# w14_MAKEYMAKEY-v03_2_3.net
KiCad netlist of a schematic drawn in EAGLE
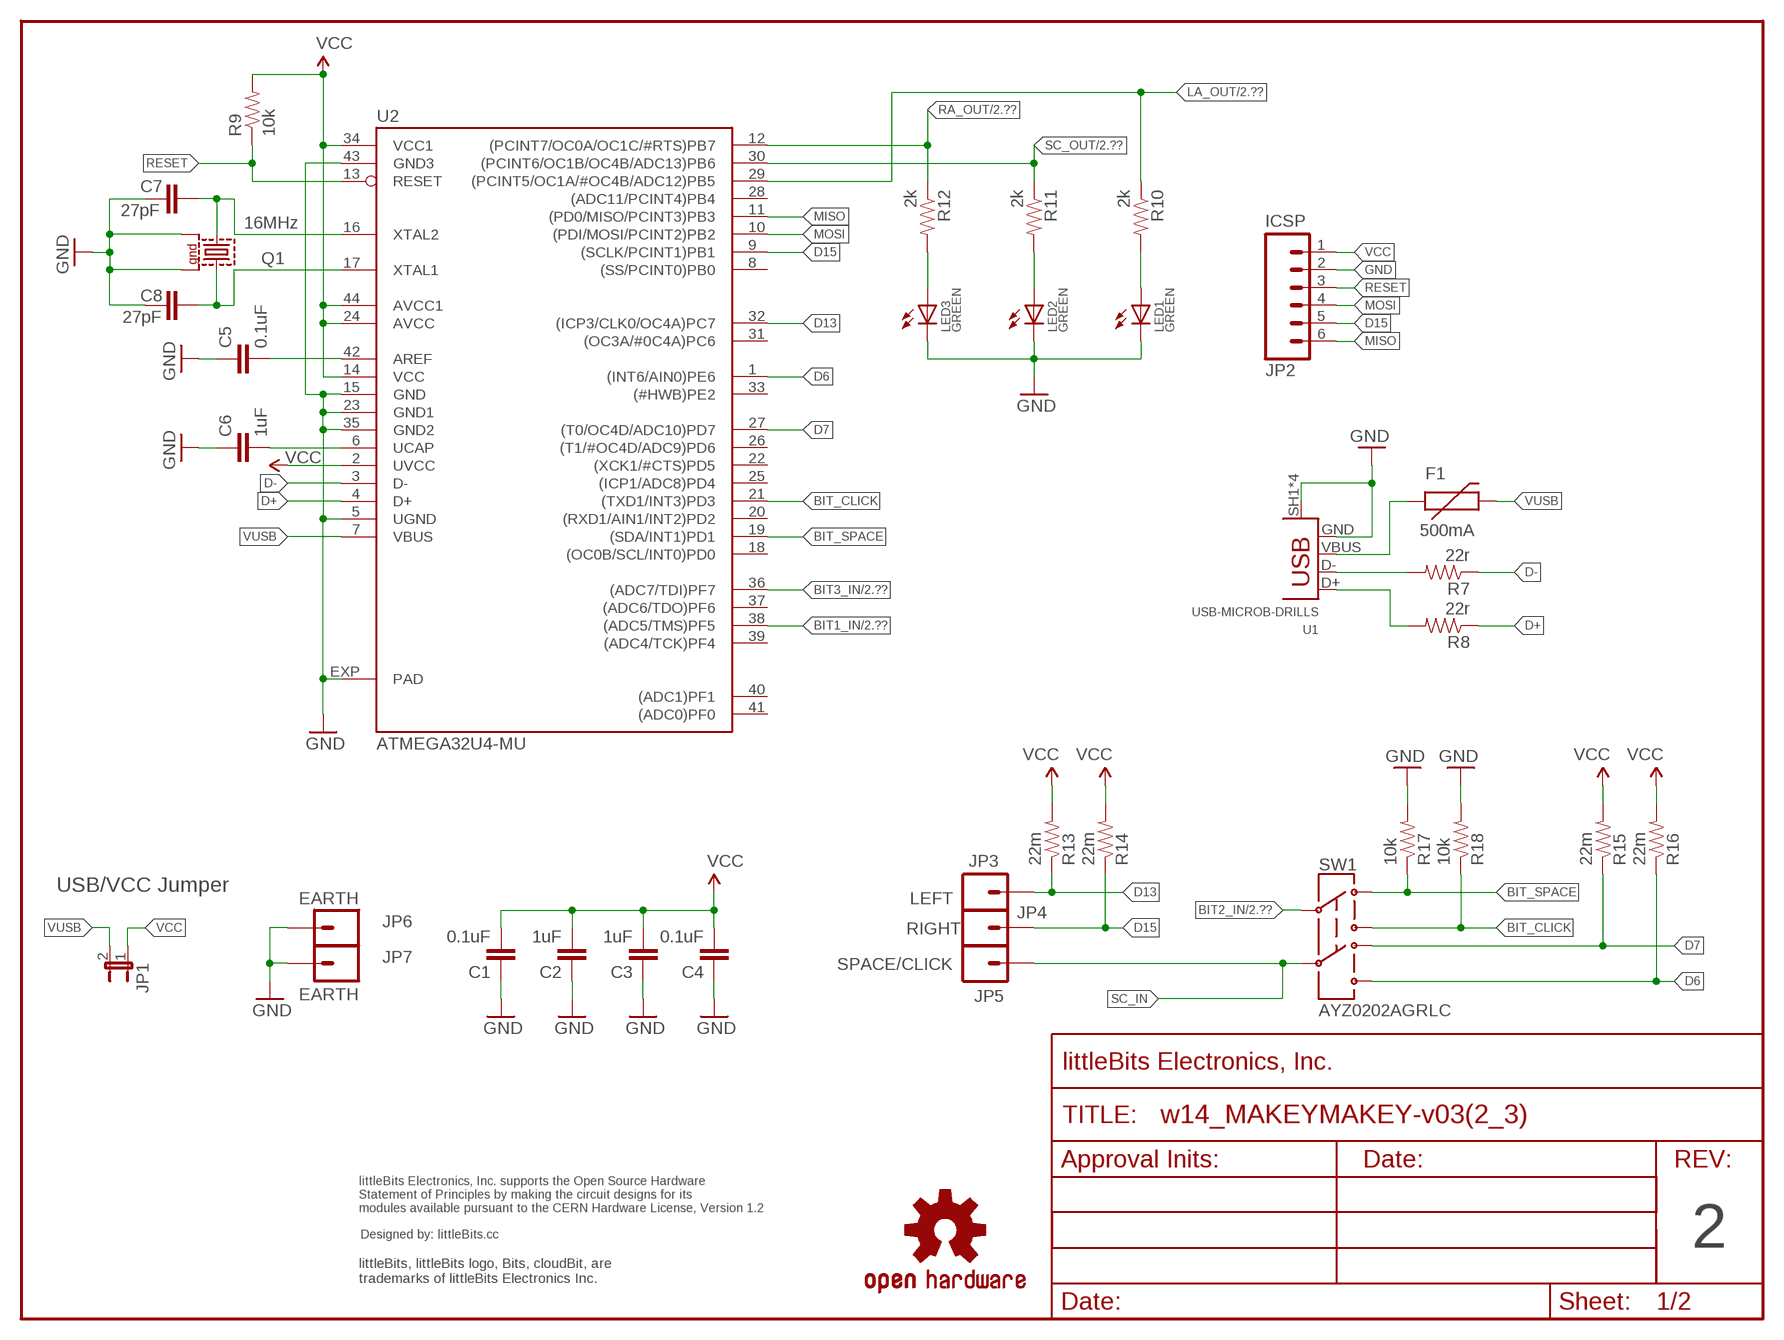
[diagram p0: schematic, sheet 1]
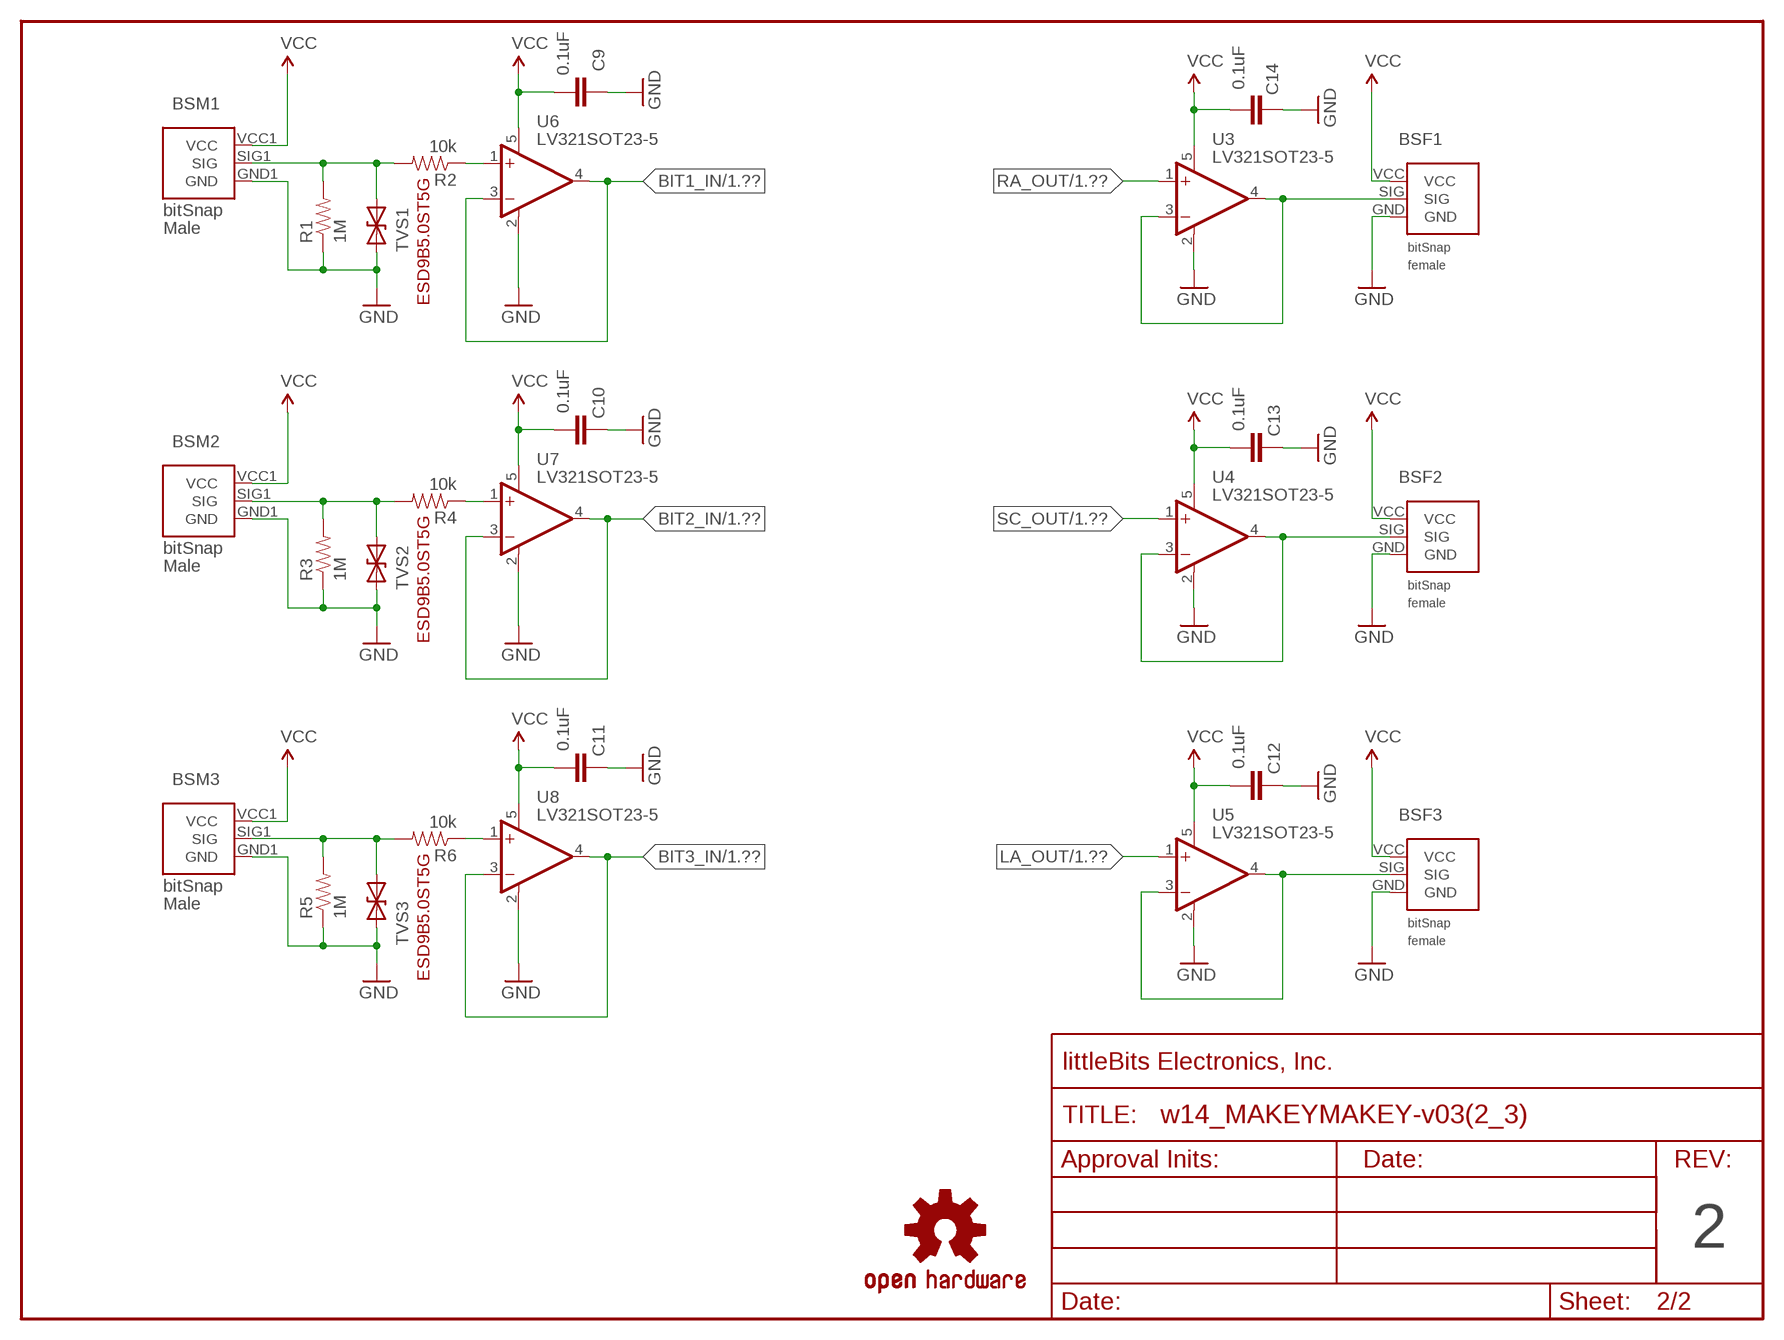
[diagram p1: schematic, sheet 2]

(export (version "E")
  (design (tool "Eeschema 10.0.6"))
  (components
    (comp (ref "C1")
      (value "0.1uF")
      (footprint "eagle-import:CAP-0603")
      (libsource (lib "eagle-import") (part "CAPCAP-0603"))
    )
    (comp (ref "C2")
      (value "1uF")
      (footprint "eagle-import:CAP-0603")
      (libsource (lib "eagle-import") (part "CAPCAP-0603"))
    )
    (comp (ref "C3")
      (value "1uF")
      (footprint "eagle-import:CAP-0603")
      (libsource (lib "eagle-import") (part "CAPCAP-0603"))
    )
    (comp (ref "C4")
      (value "0.1uF")
      (footprint "eagle-import:CAP-0603")
      (libsource (lib "eagle-import") (part "CAPCAP-0603"))
    )
    (comp (ref "C5")
      (value "0.1uF")
      (footprint "eagle-import:CAP-0603")
      (libsource (lib "eagle-import") (part "CAPCAP-0603"))
    )
    (comp (ref "C6")
      (value "1uF")
      (footprint "eagle-import:CAP-0603")
      (libsource (lib "eagle-import") (part "CAPCAP-0603"))
    )
    (comp (ref "C7")
      (value "27pF")
      (footprint "eagle-import:CAP-0603")
      (libsource (lib "eagle-import") (part "CAPCAP-0603"))
    )
    (comp (ref "C8")
      (value "27pF")
      (footprint "eagle-import:CAP-0603")
      (libsource (lib "eagle-import") (part "CAPCAP-0603"))
    )
    (comp (ref "F1")
      (value "500mA")
      (footprint "eagle-import:PTC-1206")
      (libsource (lib "eagle-import") (part "PTC"))
    )
    (comp (ref "JP1")
      (value "JUMPER-2SMD-NO")
      (footprint "eagle-import:SJ_2S-NO")
      (libsource (lib "eagle-import") (part "JUMPER-2SMD-NO"))
    )
    (comp (ref "JP2")
      (value "ICSP")
      (footprint "eagle-import:SIP6-SM-0.1IN-NOS.S.")
      (libsource (lib "eagle-import") (part "HRD-60.1INCH_NO_SILKSCREEN"))
    )
    (comp (ref "JP3")
      (value "LEFT")
      (footprint "eagle-import:1X01_ALLIGATOR_3MM")
      (libsource (lib "eagle-import") (part "M01ALLIGATOR-3MM"))
    )
    (comp (ref "JP4")
      (value "RIGHT")
      (footprint "eagle-import:1X01_ALLIGATOR_3MM")
      (libsource (lib "eagle-import") (part "M01ALLIGATOR-3MM"))
    )
    (comp (ref "JP5")
      (value "SPACE/CLICK")
      (footprint "eagle-import:1X01_ALLIGATOR_3MM")
      (libsource (lib "eagle-import") (part "M01ALLIGATOR-3MM"))
    )
    (comp (ref "JP6")
      (value "EARTH")
      (footprint "eagle-import:1X01_ALLIGATOR_3MM")
      (libsource (lib "eagle-import") (part "M01ALLIGATOR-3MM"))
    )
    (comp (ref "JP7")
      (value "EARTH")
      (footprint "eagle-import:1X01_ALLIGATOR_3MM")
      (libsource (lib "eagle-import") (part "M01ALLIGATOR-3MM"))
    )
    (comp (ref "LED1")
      (value "GREEN")
      (footprint "eagle-import:LED-1206")
      (libsource (lib "eagle-import") (part "LED1206"))
    )
    (comp (ref "LED2")
      (value "GREEN")
      (footprint "eagle-import:LED-1206")
      (libsource (lib "eagle-import") (part "LED1206"))
    )
    (comp (ref "LED3")
      (value "GREEN")
      (footprint "eagle-import:LED-1206")
      (libsource (lib "eagle-import") (part "LED1206"))
    )
    (comp (ref "Q1")
      (value "16MHz")
      (footprint "eagle-import:CRYSTAL-SMD-7B-SERIES-5X3.2MM")
      (fields (field (name "MFG") "TXC") (field (name "MPN") "7B SERIES"))
      (libsource (lib "eagle-import") (part "CRYSTAL-SMD-7B-SERIES-TXC"))
    )
    (comp (ref "R7")
      (value "22r")
      (footprint "eagle-import:RES-0603")
      (libsource (lib "eagle-import") (part "RESISTOR0603"))
    )
    (comp (ref "R8")
      (value "22r")
      (footprint "eagle-import:RES-0603")
      (libsource (lib "eagle-import") (part "RESISTOR0603"))
    )
    (comp (ref "R9")
      (value "10k")
      (footprint "eagle-import:RES-0603")
      (libsource (lib "eagle-import") (part "RESISTOR0603"))
    )
    (comp (ref "R10")
      (value "2k")
      (footprint "eagle-import:RES-0603")
      (libsource (lib "eagle-import") (part "RESISTOR0603"))
    )
    (comp (ref "R11")
      (value "2k")
      (footprint "eagle-import:RES-0603")
      (libsource (lib "eagle-import") (part "RESISTOR0603"))
    )
    (comp (ref "R12")
      (value "2k")
      (footprint "eagle-import:RES-0603")
      (libsource (lib "eagle-import") (part "RESISTOR0603"))
    )
    (comp (ref "R13")
      (value "22m")
      (footprint "eagle-import:RES-0603")
      (libsource (lib "eagle-import") (part "RESISTOR0603"))
    )
    (comp (ref "R14")
      (value "22m")
      (footprint "eagle-import:RES-0603")
      (libsource (lib "eagle-import") (part "RESISTOR0603"))
    )
    (comp (ref "R15")
      (value "22m")
      (footprint "eagle-import:RES-0603")
      (libsource (lib "eagle-import") (part "RESISTOR0603"))
    )
    (comp (ref "R16")
      (value "22m")
      (footprint "eagle-import:RES-0603")
      (libsource (lib "eagle-import") (part "RESISTOR0603"))
    )
    (comp (ref "R17")
      (value "10k")
      (footprint "eagle-import:RES-0603")
      (libsource (lib "eagle-import") (part "RESISTOR0603"))
    )
    (comp (ref "R18")
      (value "10k")
      (footprint "eagle-import:RES-0603")
      (libsource (lib "eagle-import") (part "RESISTOR0603"))
    )
    (comp (ref "SW1")
      (value "AYZ0202AGRLC")
      (footprint "eagle-import:AYZ0202")
      (libsource (lib "eagle-import") (part "AYZ0202"))
    )
    (comp (ref "U$1")
      (value "OSHWCREDIT")
      (footprint "eagle-import:OSHWCREDIT")
      (libsource (lib "eagle-import") (part "OSHWCREDIT"))
    )
    (comp (ref "U$58")
      (value "FRAME-LETTER-OHWOHW")
      (footprint "eagle-import:FABDWG01-OHW")
      (libsource (lib "eagle-import") (part "FRAME-LETTER-OHWOHW"))
    )
    (comp (ref "U$70")
      (value "OSHW-LOGOL")
      (footprint "eagle-import:OSHW-LOGO-L")
      (libsource (lib "eagle-import") (part "OSHW-LOGOL"))
    )
    (comp (ref "U1")
      (value "USB-MICROB-DRILLS")
      (footprint "eagle-import:USB-MICROB-AUK-DRILLS")
      (fields (field (name "MFG") "AUK") (field (name "MPN") "MCSB5ABSW-4-GXX-R1K-H"))
      (libsource (lib "eagle-import") (part "USB-MICROB-DRILLS"))
    )
    (comp (ref "U2")
      (value "ATMEGA32U4-MU")
      (footprint "eagle-import:QFN44ML7X7")
      (libsource (lib "eagle-import") (part "ATMEGA32U4-XUMU"))
    )
    (comp (ref "BSF1")
      (value "BITSNAP_V03_FEMALE")
      (footprint "eagle-import:BITSNAP_V03_FEMALE")
      (libsource (lib "eagle-import") (part "BITSNAP_V03_FEMALE"))
    )
    (comp (ref "BSF2")
      (value "BITSNAP_V03_FEMALE")
      (footprint "eagle-import:BITSNAP_V03_FEMALE")
      (libsource (lib "eagle-import") (part "BITSNAP_V03_FEMALE"))
    )
    (comp (ref "BSF3")
      (value "BITSNAP_V03_FEMALE")
      (footprint "eagle-import:BITSNAP_V03_FEMALE")
      (libsource (lib "eagle-import") (part "BITSNAP_V03_FEMALE"))
    )
    (comp (ref "BSM1")
      (value "BITSNAP_V03_MALE")
      (footprint "eagle-import:BITSNAP_V03_MALE")
      (libsource (lib "eagle-import") (part "BITSNAP_V03_MALE"))
    )
    (comp (ref "BSM2")
      (value "BITSNAP_V03_MALE")
      (footprint "eagle-import:BITSNAP_V03_MALE")
      (libsource (lib "eagle-import") (part "BITSNAP_V03_MALE"))
    )
    (comp (ref "BSM3")
      (value "BITSNAP_V03_MALE")
      (footprint "eagle-import:BITSNAP_V03_MALE")
      (libsource (lib "eagle-import") (part "BITSNAP_V03_MALE"))
    )
    (comp (ref "C9")
      (value "0.1uF")
      (footprint "eagle-import:CAP-0603")
      (libsource (lib "eagle-import") (part "CAPCAP-0603"))
    )
    (comp (ref "C10")
      (value "0.1uF")
      (footprint "eagle-import:CAP-0603")
      (libsource (lib "eagle-import") (part "CAPCAP-0603"))
    )
    (comp (ref "C11")
      (value "0.1uF")
      (footprint "eagle-import:CAP-0603")
      (libsource (lib "eagle-import") (part "CAPCAP-0603"))
    )
    (comp (ref "C12")
      (value "0.1uF")
      (footprint "eagle-import:CAP-0603")
      (libsource (lib "eagle-import") (part "CAPCAP-0603"))
    )
    (comp (ref "C13")
      (value "0.1uF")
      (footprint "eagle-import:CAP-0603")
      (libsource (lib "eagle-import") (part "CAPCAP-0603"))
    )
    (comp (ref "C14")
      (value "0.1uF")
      (footprint "eagle-import:CAP-0603")
      (libsource (lib "eagle-import") (part "CAPCAP-0603"))
    )
    (comp (ref "R1")
      (value "1M")
      (footprint "eagle-import:RES-0603")
      (libsource (lib "eagle-import") (part "RESISTOR0603"))
    )
    (comp (ref "R2")
      (value "10k")
      (footprint "eagle-import:RES-0603")
      (libsource (lib "eagle-import") (part "RESISTOR0603"))
    )
    (comp (ref "R3")
      (value "1M")
      (footprint "eagle-import:RES-0603")
      (libsource (lib "eagle-import") (part "RESISTOR0603"))
    )
    (comp (ref "R4")
      (value "10k")
      (footprint "eagle-import:RES-0603")
      (libsource (lib "eagle-import") (part "RESISTOR0603"))
    )
    (comp (ref "R5")
      (value "1M")
      (footprint "eagle-import:RES-0603")
      (libsource (lib "eagle-import") (part "RESISTOR0603"))
    )
    (comp (ref "R6")
      (value "10k")
      (footprint "eagle-import:RES-0603")
      (libsource (lib "eagle-import") (part "RESISTOR0603"))
    )
    (comp (ref "TVS1")
      (value "ESD9B5.0ST5G")
      (footprint "eagle-import:SOD-923")
      (fields (field (name "MPN") "ESD9B5.0ST5G"))
      (libsource (lib "eagle-import") (part "DIODE-TVSSOD-923"))
    )
    (comp (ref "TVS2")
      (value "ESD9B5.0ST5G")
      (footprint "eagle-import:SOD-923")
      (fields (field (name "MPN") "ESD9B5.0ST5G"))
      (libsource (lib "eagle-import") (part "DIODE-TVSSOD-923"))
    )
    (comp (ref "TVS3")
      (value "ESD9B5.0ST5G")
      (footprint "eagle-import:SOD-923")
      (fields (field (name "MPN") "ESD9B5.0ST5G"))
      (libsource (lib "eagle-import") (part "DIODE-TVSSOD-923"))
    )
    (comp (ref "U$2")
      (value "FRAME-LETTER-OHWOHW")
      (footprint "eagle-import:FABDWG01-OHW")
      (libsource (lib "eagle-import") (part "FRAME-LETTER-OHWOHW"))
    )
    (comp (ref "U$56")
      (value "OSHW-LOGOL")
      (footprint "eagle-import:OSHW-LOGO-L")
      (libsource (lib "eagle-import") (part "OSHW-LOGOL"))
    )
    (comp (ref "U3")
      (value "LV321SOT23-5")
      (footprint "eagle-import:SOT23-5")
      (libsource (lib "eagle-import") (part "LV321SOT23-5"))
    )
    (comp (ref "U4")
      (value "LV321SOT23-5")
      (footprint "eagle-import:SOT23-5")
      (libsource (lib "eagle-import") (part "LV321SOT23-5"))
    )
    (comp (ref "U5")
      (value "LV321SOT23-5")
      (footprint "eagle-import:SOT23-5")
      (libsource (lib "eagle-import") (part "LV321SOT23-5"))
    )
    (comp (ref "U6")
      (value "LV321SOT23-5")
      (footprint "eagle-import:SOT23-5")
      (libsource (lib "eagle-import") (part "LV321SOT23-5"))
    )
    (comp (ref "U7")
      (value "LV321SOT23-5")
      (footprint "eagle-import:SOT23-5")
      (libsource (lib "eagle-import") (part "LV321SOT23-5"))
    )
    (comp (ref "U8")
      (value "LV321SOT23-5")
      (footprint "eagle-import:SOT23-5")
      (libsource (lib "eagle-import") (part "LV321SOT23-5"))
    )
  )
  (nets
    (net (code "1") (name "BIT1_IN") (class "Default")
      (node (ref "U2") (pin "38") (pinfunction "(ADC5/TMS)PF5_38") (pintype "bidirectional"))
      (node (ref "U6") (pin "3") (pinfunction "-IN_3") (pintype "input"))
      (node (ref "U6") (pin "4") (pinfunction "OUT_4") (pintype "output"))
    )
    (net (code "2") (name "BIT2_IN") (class "Default")
      (node (ref "SW1") (pin "2") (pinfunction "2_2") (pintype "bidirectional"))
      (node (ref "U7") (pin "3") (pinfunction "-IN_3") (pintype "input"))
      (node (ref "U7") (pin "4") (pinfunction "OUT_4") (pintype "output"))
    )
    (net (code "3") (name "BIT3_IN") (class "Default")
      (node (ref "U2") (pin "36") (pinfunction "(ADC7/TDI)PF7_36") (pintype "bidirectional"))
      (node (ref "U8") (pin "3") (pinfunction "-IN_3") (pintype "input"))
      (node (ref "U8") (pin "4") (pinfunction "OUT_4") (pintype "output"))
    )
    (net (code "4") (name "BIT_CLICK") (class "Default")
      (node (ref "R18") (pin "1") (pinfunction "1_1") (pintype "passive"))
      (node (ref "SW1") (pin "3") (pinfunction "3_3") (pintype "bidirectional"))
      (node (ref "U2") (pin "21") (pinfunction "(TXD1/INT3)PD3_21") (pintype "bidirectional"))
    )
    (net (code "5") (name "BIT_SPACE") (class "Default")
      (node (ref "R17") (pin "1") (pinfunction "1_1") (pintype "passive"))
      (node (ref "SW1") (pin "1") (pinfunction "1_1") (pintype "bidirectional"))
      (node (ref "U2") (pin "19") (pinfunction "(SDA/INT1)PD1_19") (pintype "bidirectional"))
    )
    (net (code "6") (name "D+") (class "Default")
      (node (ref "R8") (pin "1") (pinfunction "1_1") (pintype "passive"))
      (node (ref "U2") (pin "4") (pinfunction "D+_4") (pintype "bidirectional"))
    )
    (net (code "7") (name "D-") (class "Default")
      (node (ref "R7") (pin "1") (pinfunction "1_1") (pintype "passive"))
      (node (ref "U2") (pin "3") (pinfunction "D-_3") (pintype "bidirectional"))
    )
    (net (code "8") (name "D6") (class "Default")
      (node (ref "R16") (pin "1") (pinfunction "1_1") (pintype "passive"))
      (node (ref "SW1") (pin "6") (pinfunction "6_6") (pintype "bidirectional"))
      (node (ref "U2") (pin "1") (pinfunction "(INT6/AIN0)PE6_1") (pintype "bidirectional"))
    )
    (net (code "9") (name "D7") (class "Default")
      (node (ref "R15") (pin "1") (pinfunction "1_1") (pintype "passive"))
      (node (ref "SW1") (pin "4") (pinfunction "4_4") (pintype "bidirectional"))
      (node (ref "U2") (pin "27") (pinfunction "(T0/OC4D/ADC10)PD7_27") (pintype "bidirectional"))
    )
    (net (code "10") (name "D13") (class "Default")
      (node (ref "JP3") (pin "1@0") (pinfunction "1_1@0") (pintype "passive"))
      (node (ref "JP3") (pin "1@2") (pinfunction "1_1@2") (pintype "passive"))
      (node (ref "R13") (pin "1") (pinfunction "1_1") (pintype "passive"))
      (node (ref "U2") (pin "32") (pinfunction "(ICP3/CLK0/OC4A)PC7_32") (pintype "bidirectional"))
    )
    (net (code "11") (name "D15") (class "Default")
      (node (ref "JP2") (pin "5") (pinfunction "5_5") (pintype "passive"))
      (node (ref "JP4") (pin "1@0") (pinfunction "1_1@0") (pintype "passive"))
      (node (ref "JP4") (pin "1@2") (pinfunction "1_1@2") (pintype "passive"))
      (node (ref "R14") (pin "1") (pinfunction "1_1") (pintype "passive"))
      (node (ref "U2") (pin "9") (pinfunction "(SCLK/PCINT1)PB1_9") (pintype "bidirectional"))
    )
    (net (code "12") (name "GND") (class "Default")
      (node (ref "BSF1") (pin "GND") (pinfunction "GND_GND") (pintype "bidirectional"))
      (node (ref "BSF2") (pin "GND") (pinfunction "GND_GND") (pintype "bidirectional"))
      (node (ref "BSF3") (pin "GND") (pinfunction "GND_GND") (pintype "bidirectional"))
      (node (ref "BSM1") (pin "GND1") (pinfunction "GND_GND1") (pintype "bidirectional"))
      (node (ref "BSM2") (pin "GND1") (pinfunction "GND_GND1") (pintype "bidirectional"))
      (node (ref "BSM3") (pin "GND1") (pinfunction "GND_GND1") (pintype "bidirectional"))
      (node (ref "C1") (pin "1") (pinfunction "1_1") (pintype "passive"))
      (node (ref "C10") (pin "1") (pinfunction "1_1") (pintype "passive"))
      (node (ref "C11") (pin "1") (pinfunction "1_1") (pintype "passive"))
      (node (ref "C12") (pin "1") (pinfunction "1_1") (pintype "passive"))
      (node (ref "C13") (pin "1") (pinfunction "1_1") (pintype "passive"))
      (node (ref "C14") (pin "1") (pinfunction "1_1") (pintype "passive"))
      (node (ref "C2") (pin "1") (pinfunction "1_1") (pintype "passive"))
      (node (ref "C3") (pin "2") (pinfunction "2_2") (pintype "passive"))
      (node (ref "C4") (pin "1") (pinfunction "1_1") (pintype "passive"))
      (node (ref "C5") (pin "1") (pinfunction "1_1") (pintype "passive"))
      (node (ref "C6") (pin "1") (pinfunction "1_1") (pintype "passive"))
      (node (ref "C7") (pin "2") (pinfunction "2_2") (pintype "passive"))
      (node (ref "C8") (pin "2") (pinfunction "2_2") (pintype "passive"))
      (node (ref "C9") (pin "1") (pinfunction "1_1") (pintype "passive"))
      (node (ref "JP2") (pin "2") (pinfunction "2_2") (pintype "passive"))
      (node (ref "JP6") (pin "1@0") (pinfunction "1_1@0") (pintype "passive"))
      (node (ref "JP6") (pin "1@2") (pinfunction "1_1@2") (pintype "passive"))
      (node (ref "JP7") (pin "1@0") (pinfunction "1_1@0") (pintype "passive"))
      (node (ref "JP7") (pin "1@2") (pinfunction "1_1@2") (pintype "passive"))
      (node (ref "LED1") (pin "C") (pinfunction "C_C") (pintype "passive"))
      (node (ref "LED2") (pin "C") (pinfunction "C_C") (pintype "passive"))
      (node (ref "LED3") (pin "C") (pinfunction "C_C") (pintype "passive"))
      (node (ref "Q1") (pin "P$2") (pinfunction "2_P$2") (pintype "passive"))
      (node (ref "Q1") (pin "P$4") (pinfunction "4_P$4") (pintype "passive"))
      (node (ref "R1") (pin "1") (pinfunction "1_1") (pintype "passive"))
      (node (ref "R17") (pin "2") (pinfunction "2_2") (pintype "passive"))
      (node (ref "R18") (pin "2") (pinfunction "2_2") (pintype "passive"))
      (node (ref "R3") (pin "1") (pinfunction "1_1") (pintype "passive"))
      (node (ref "R5") (pin "1") (pinfunction "1_1") (pintype "passive"))
      (node (ref "TVS1") (pin "1") (pinfunction "A_1") (pintype "passive"))
      (node (ref "TVS2") (pin "1") (pinfunction "A_1") (pintype "passive"))
      (node (ref "TVS3") (pin "1") (pinfunction "A_1") (pintype "passive"))
      (node (ref "U1") (pin "GND") (pinfunction "GND_GND") (pintype "bidirectional"))
      (node (ref "U1") (pin "SH1") (pinfunction "SH_SH1") (pintype "bidirectional"))
      (node (ref "U1") (pin "SH2") (pinfunction "SH_SH2") (pintype "bidirectional"))
      (node (ref "U1") (pin "SH3") (pinfunction "SH_SH3") (pintype "bidirectional"))
      (node (ref "U1") (pin "SH4") (pinfunction "SH_SH4") (pintype "bidirectional"))
      (node (ref "U2") (pin "15") (pinfunction "GND_15") (pintype "power_in"))
      (node (ref "U2") (pin "23") (pinfunction "GND1_23") (pintype "power_in"))
      (node (ref "U2") (pin "35") (pinfunction "GND2_35") (pintype "power_in"))
      (node (ref "U2") (pin "43") (pinfunction "GND3_43") (pintype "power_in"))
      (node (ref "U2") (pin "5") (pinfunction "UGND_5") (pintype "power_in"))
      (node (ref "U2") (pin "EXP") (pinfunction "PAD_EXP") (pintype "power_in"))
      (node (ref "U3") (pin "2") (pinfunction "V-_2") (pintype "power_in"))
      (node (ref "U4") (pin "2") (pinfunction "V-_2") (pintype "power_in"))
      (node (ref "U5") (pin "2") (pinfunction "V-_2") (pintype "power_in"))
      (node (ref "U6") (pin "2") (pinfunction "V-_2") (pintype "power_in"))
      (node (ref "U7") (pin "2") (pinfunction "V-_2") (pintype "power_in"))
      (node (ref "U8") (pin "2") (pinfunction "V-_2") (pintype "power_in"))
    )
    (net (code "13") (name "LA_OUT") (class "Default")
      (node (ref "R10") (pin "1") (pinfunction "1_1") (pintype "passive"))
      (node (ref "U2") (pin "29") (pinfunction "(PCINT5/OC1A/#OC4B/ADC12)PB5_29") (pintype "bidirectional"))
      (node (ref "U5") (pin "1") (pinfunction "+IN_1") (pintype "input"))
    )
    (net (code "14") (name "MISO") (class "Default")
      (node (ref "JP2") (pin "6") (pinfunction "6_6") (pintype "passive"))
      (node (ref "U2") (pin "11") (pinfunction "(PD0/MISO/PCINT3)PB3_11") (pintype "bidirectional"))
    )
    (net (code "15") (name "MOSI") (class "Default")
      (node (ref "JP2") (pin "4") (pinfunction "4_4") (pintype "passive"))
      (node (ref "U2") (pin "10") (pinfunction "(PDI/MOSI/PCINT2)PB2_10") (pintype "bidirectional"))
    )
    (net (code "16") (name "Net-(BSM1-SIG)") (class "Default")
      (node (ref "BSM1") (pin "SIG1") (pinfunction "SIG_SIG1") (pintype "bidirectional"))
      (node (ref "R1") (pin "2") (pinfunction "2_2") (pintype "passive"))
      (node (ref "R2") (pin "2") (pinfunction "2_2") (pintype "passive"))
      (node (ref "TVS1") (pin "2") (pinfunction "C_2") (pintype "passive"))
    )
    (net (code "17") (name "Net-(BSM2-SIG)") (class "Default")
      (node (ref "BSM2") (pin "SIG1") (pinfunction "SIG_SIG1") (pintype "bidirectional"))
      (node (ref "R3") (pin "2") (pinfunction "2_2") (pintype "passive"))
      (node (ref "R4") (pin "2") (pinfunction "2_2") (pintype "passive"))
      (node (ref "TVS2") (pin "2") (pinfunction "C_2") (pintype "passive"))
    )
    (net (code "18") (name "Net-(BSM3-SIG)") (class "Default")
      (node (ref "BSM3") (pin "SIG1") (pinfunction "SIG_SIG1") (pintype "bidirectional"))
      (node (ref "R5") (pin "2") (pinfunction "2_2") (pintype "passive"))
      (node (ref "R6") (pin "2") (pinfunction "2_2") (pintype "passive"))
      (node (ref "TVS3") (pin "2") (pinfunction "C_2") (pintype "passive"))
    )
    (net (code "19") (name "Net-(F1-Pad1)") (class "Default")
      (node (ref "F1") (pin "1") (pinfunction "1_1") (pintype "bidirectional"))
      (node (ref "U1") (pin "VBUS") (pinfunction "VBUS_VBUS") (pintype "bidirectional"))
    )
    (net (code "20") (name "Net-(LED1-PadA)") (class "Default")
      (node (ref "LED1") (pin "A") (pinfunction "A_A") (pintype "passive"))
      (node (ref "R10") (pin "2") (pinfunction "2_2") (pintype "passive"))
    )
    (net (code "21") (name "Net-(LED2-PadA)") (class "Default")
      (node (ref "LED2") (pin "A") (pinfunction "A_A") (pintype "passive"))
      (node (ref "R11") (pin "2") (pinfunction "2_2") (pintype "passive"))
    )
    (net (code "22") (name "Net-(LED3-PadA)") (class "Default")
      (node (ref "LED3") (pin "A") (pinfunction "A_A") (pintype "passive"))
      (node (ref "R12") (pin "2") (pinfunction "2_2") (pintype "passive"))
    )
    (net (code "23") (name "Net-(Q1-1)") (class "Default")
      (node (ref "C8") (pin "1") (pinfunction "1_1") (pintype "passive"))
      (node (ref "Q1") (pin "P$1") (pinfunction "1_P$1") (pintype "passive"))
      (node (ref "U2") (pin "17") (pinfunction "XTAL1_17") (pintype "bidirectional"))
    )
    (net (code "24") (name "Net-(Q1-3)") (class "Default")
      (node (ref "C7") (pin "1") (pinfunction "1_1") (pintype "passive"))
      (node (ref "Q1") (pin "P$3") (pinfunction "3_P$3") (pintype "passive"))
      (node (ref "U2") (pin "16") (pinfunction "XTAL2_16") (pintype "bidirectional"))
    )
    (net (code "25") (name "Net-(R7-Pad2)") (class "Default")
      (node (ref "R7") (pin "2") (pinfunction "2_2") (pintype "passive"))
      (node (ref "U1") (pin "D-") (pinfunction "D-_D-") (pintype "bidirectional"))
    )
    (net (code "26") (name "Net-(R8-Pad2)") (class "Default")
      (node (ref "R8") (pin "2") (pinfunction "2_2") (pintype "passive"))
      (node (ref "U1") (pin "D+") (pinfunction "D+_D+") (pintype "bidirectional"))
    )
    (net (code "27") (name "Net-(U2-AREF)") (class "Default")
      (node (ref "C5") (pin "2") (pinfunction "2_2") (pintype "passive"))
      (node (ref "U2") (pin "42") (pinfunction "AREF_42") (pintype "power_in"))
    )
    (net (code "28") (name "Net-(U2-UCAP)") (class "Default")
      (node (ref "C6") (pin "2") (pinfunction "2_2") (pintype "passive"))
      (node (ref "U2") (pin "6") (pinfunction "UCAP_6") (pintype "passive"))
    )
    (net (code "29") (name "Net-(U3--IN)") (class "Default")
      (node (ref "BSF1") (pin "SIG") (pinfunction "SIG_SIG") (pintype "bidirectional"))
      (node (ref "U3") (pin "3") (pinfunction "-IN_3") (pintype "input"))
      (node (ref "U3") (pin "4") (pinfunction "OUT_4") (pintype "output"))
    )
    (net (code "30") (name "Net-(U4--IN)") (class "Default")
      (node (ref "BSF2") (pin "SIG") (pinfunction "SIG_SIG") (pintype "bidirectional"))
      (node (ref "U4") (pin "3") (pinfunction "-IN_3") (pintype "input"))
      (node (ref "U4") (pin "4") (pinfunction "OUT_4") (pintype "output"))
    )
    (net (code "31") (name "Net-(U5--IN)") (class "Default")
      (node (ref "BSF3") (pin "SIG") (pinfunction "SIG_SIG") (pintype "bidirectional"))
      (node (ref "U5") (pin "3") (pinfunction "-IN_3") (pintype "input"))
      (node (ref "U5") (pin "4") (pinfunction "OUT_4") (pintype "output"))
    )
    (net (code "32") (name "Net-(U6-+IN)") (class "Default")
      (node (ref "R2") (pin "1") (pinfunction "1_1") (pintype "passive"))
      (node (ref "U6") (pin "1") (pinfunction "+IN_1") (pintype "input"))
    )
    (net (code "33") (name "Net-(U7-+IN)") (class "Default")
      (node (ref "R4") (pin "1") (pinfunction "1_1") (pintype "passive"))
      (node (ref "U7") (pin "1") (pinfunction "+IN_1") (pintype "input"))
    )
    (net (code "34") (name "Net-(U8-+IN)") (class "Default")
      (node (ref "R6") (pin "1") (pinfunction "1_1") (pintype "passive"))
      (node (ref "U8") (pin "1") (pinfunction "+IN_1") (pintype "input"))
    )
    (net (code "35") (name "RA_OUT") (class "Default")
      (node (ref "R12") (pin "1") (pinfunction "1_1") (pintype "passive"))
      (node (ref "U2") (pin "12") (pinfunction "(PCINT7/OC0A/OC1C/#RTS)PB7_12") (pintype "bidirectional"))
      (node (ref "U3") (pin "1") (pinfunction "+IN_1") (pintype "input"))
    )
    (net (code "36") (name "RESET") (class "Default")
      (node (ref "JP2") (pin "3") (pinfunction "3_3") (pintype "passive"))
      (node (ref "R9") (pin "1") (pinfunction "1_1") (pintype "passive"))
      (node (ref "U2") (pin "13") (pinfunction "RESET_13") (pintype "input"))
    )
    (net (code "37") (name "SC_IN") (class "Default")
      (node (ref "JP5") (pin "1@0") (pinfunction "1_1@0") (pintype "passive"))
      (node (ref "JP5") (pin "1@2") (pinfunction "1_1@2") (pintype "passive"))
      (node (ref "SW1") (pin "5") (pinfunction "5_5") (pintype "bidirectional"))
    )
    (net (code "38") (name "SC_OUT") (class "Default")
      (node (ref "R11") (pin "1") (pinfunction "1_1") (pintype "passive"))
      (node (ref "U2") (pin "30") (pinfunction "(PCINT6/OC1B/OC4B/ADC13)PB6_30") (pintype "bidirectional"))
      (node (ref "U4") (pin "1") (pinfunction "+IN_1") (pintype "input"))
    )
    (net (code "39") (name "VCC") (class "Default")
      (node (ref "BSF1") (pin "VCC") (pinfunction "VCC_VCC") (pintype "bidirectional"))
      (node (ref "BSF2") (pin "VCC") (pinfunction "VCC_VCC") (pintype "bidirectional"))
      (node (ref "BSF3") (pin "VCC") (pinfunction "VCC_VCC") (pintype "bidirectional"))
      (node (ref "BSM1") (pin "VCC1") (pinfunction "VCC_VCC1") (pintype "bidirectional"))
      (node (ref "BSM2") (pin "VCC1") (pinfunction "VCC_VCC1") (pintype "bidirectional"))
      (node (ref "BSM3") (pin "VCC1") (pinfunction "VCC_VCC1") (pintype "bidirectional"))
      (node (ref "C1") (pin "2") (pinfunction "2_2") (pintype "passive"))
      (node (ref "C10") (pin "2") (pinfunction "2_2") (pintype "passive"))
      (node (ref "C11") (pin "2") (pinfunction "2_2") (pintype "passive"))
      (node (ref "C12") (pin "2") (pinfunction "2_2") (pintype "passive"))
      (node (ref "C13") (pin "2") (pinfunction "2_2") (pintype "passive"))
      (node (ref "C14") (pin "2") (pinfunction "2_2") (pintype "passive"))
      (node (ref "C2") (pin "2") (pinfunction "2_2") (pintype "passive"))
      (node (ref "C3") (pin "1") (pinfunction "1_1") (pintype "passive"))
      (node (ref "C4") (pin "2") (pinfunction "2_2") (pintype "passive"))
      (node (ref "C9") (pin "2") (pinfunction "2_2") (pintype "passive"))
      (node (ref "JP1") (pin "1") (pinfunction "1_1") (pintype "passive"))
      (node (ref "JP2") (pin "1") (pinfunction "1_1") (pintype "passive"))
      (node (ref "R13") (pin "2") (pinfunction "2_2") (pintype "passive"))
      (node (ref "R14") (pin "2") (pinfunction "2_2") (pintype "passive"))
      (node (ref "R15") (pin "2") (pinfunction "2_2") (pintype "passive"))
      (node (ref "R16") (pin "2") (pinfunction "2_2") (pintype "passive"))
      (node (ref "R9") (pin "2") (pinfunction "2_2") (pintype "passive"))
      (node (ref "U2") (pin "14") (pinfunction "VCC_14") (pintype "power_in"))
      (node (ref "U2") (pin "2") (pinfunction "UVCC_2") (pintype "power_in"))
      (node (ref "U2") (pin "24") (pinfunction "AVCC_24") (pintype "power_in"))
      (node (ref "U2") (pin "34") (pinfunction "VCC1_34") (pintype "power_in"))
      (node (ref "U2") (pin "44") (pinfunction "AVCC1_44") (pintype "power_in"))
      (node (ref "U3") (pin "5") (pinfunction "V+_5") (pintype "power_in"))
      (node (ref "U4") (pin "5") (pinfunction "V+_5") (pintype "power_in"))
      (node (ref "U5") (pin "5") (pinfunction "V+_5") (pintype "power_in"))
      (node (ref "U6") (pin "5") (pinfunction "V+_5") (pintype "power_in"))
      (node (ref "U7") (pin "5") (pinfunction "V+_5") (pintype "power_in"))
      (node (ref "U8") (pin "5") (pinfunction "V+_5") (pintype "power_in"))
    )
    (net (code "40") (name "VUSB") (class "Default")
      (node (ref "F1") (pin "2") (pinfunction "2_2") (pintype "bidirectional"))
      (node (ref "JP1") (pin "2") (pinfunction "2_2") (pintype "passive"))
      (node (ref "U2") (pin "7") (pinfunction "VBUS_7") (pintype "input"))
    )
    (net (code "41") (name "unconnected-(U2-(#HWB)PE2-Pad33)") (class "Default")
      (node (ref "U2") (pin "33") (pinfunction "(#HWB)PE2_33") (pintype "bidirectional"))
    )
    (net (code "42") (name "unconnected-(U2-(ADC0)PF0-Pad41)") (class "Default")
      (node (ref "U2") (pin "41") (pinfunction "(ADC0)PF0_41") (pintype "bidirectional"))
    )
    (net (code "43") (name "unconnected-(U2-(ADC1)PF1-Pad40)") (class "Default")
      (node (ref "U2") (pin "40") (pinfunction "(ADC1)PF1_40") (pintype "bidirectional"))
    )
    (net (code "44") (name "unconnected-(U2-(ADC4{slash}TCK)PF4-Pad39)") (class "Default")
      (node (ref "U2") (pin "39") (pinfunction "(ADC4/TCK)PF4_39") (pintype "bidirectional"))
    )
    (net (code "45") (name "unconnected-(U2-(ADC6{slash}TDO)PF6-Pad37)") (class "Default")
      (node (ref "U2") (pin "37") (pinfunction "(ADC6/TDO)PF6_37") (pintype "bidirectional"))
    )
    (net (code "46") (name "unconnected-(U2-(ADC11{slash}PCINT4)PB4-Pad28)") (class "Default")
      (node (ref "U2") (pin "28") (pinfunction "(ADC11/PCINT4)PB4_28") (pintype "bidirectional"))
    )
    (net (code "47") (name "unconnected-(U2-(ICP1{slash}ADC8)PD4-Pad25)") (class "Default")
      (node (ref "U2") (pin "25") (pinfunction "(ICP1/ADC8)PD4_25") (pintype "bidirectional"))
    )
    (net (code "48") (name "unconnected-(U2-(OC0B{slash}SCL{slash}INT0)PD0-Pad18)") (class "Default")
      (node (ref "U2") (pin "18") (pinfunction "(OC0B/SCL/INT0)PD0_18") (pintype "bidirectional"))
    )
    (net (code "49") (name "unconnected-(U2-(OC3A{slash}#0C4A)PC6-Pad31)") (class "Default")
      (node (ref "U2") (pin "31") (pinfunction "(OC3A/#0C4A)PC6_31") (pintype "bidirectional"))
    )
    (net (code "50") (name "unconnected-(U2-(RXD1{slash}AIN1{slash}INT2)PD2-Pad20)") (class "Default")
      (node (ref "U2") (pin "20") (pinfunction "(RXD1/AIN1/INT2)PD2_20") (pintype "bidirectional"))
    )
    (net (code "51") (name "unconnected-(U2-(SS{slash}PCINT0)PB0-Pad8)") (class "Default")
      (node (ref "U2") (pin "8") (pinfunction "(SS/PCINT0)PB0_8") (pintype "bidirectional"))
    )
    (net (code "52") (name "unconnected-(U2-(T1{slash}#OC4D{slash}ADC9)PD6-Pad26)") (class "Default")
      (node (ref "U2") (pin "26") (pinfunction "(T1/#OC4D/ADC9)PD6_26") (pintype "bidirectional"))
    )
    (net (code "53") (name "unconnected-(U2-(XCK1{slash}#CTS)PD5-Pad22)") (class "Default")
      (node (ref "U2") (pin "22") (pinfunction "(XCK1/#CTS)PD5_22") (pintype "bidirectional"))
    )
  )
)
